# Sheet1.net
KiCad netlist of a schematic drawn in Altium Designer
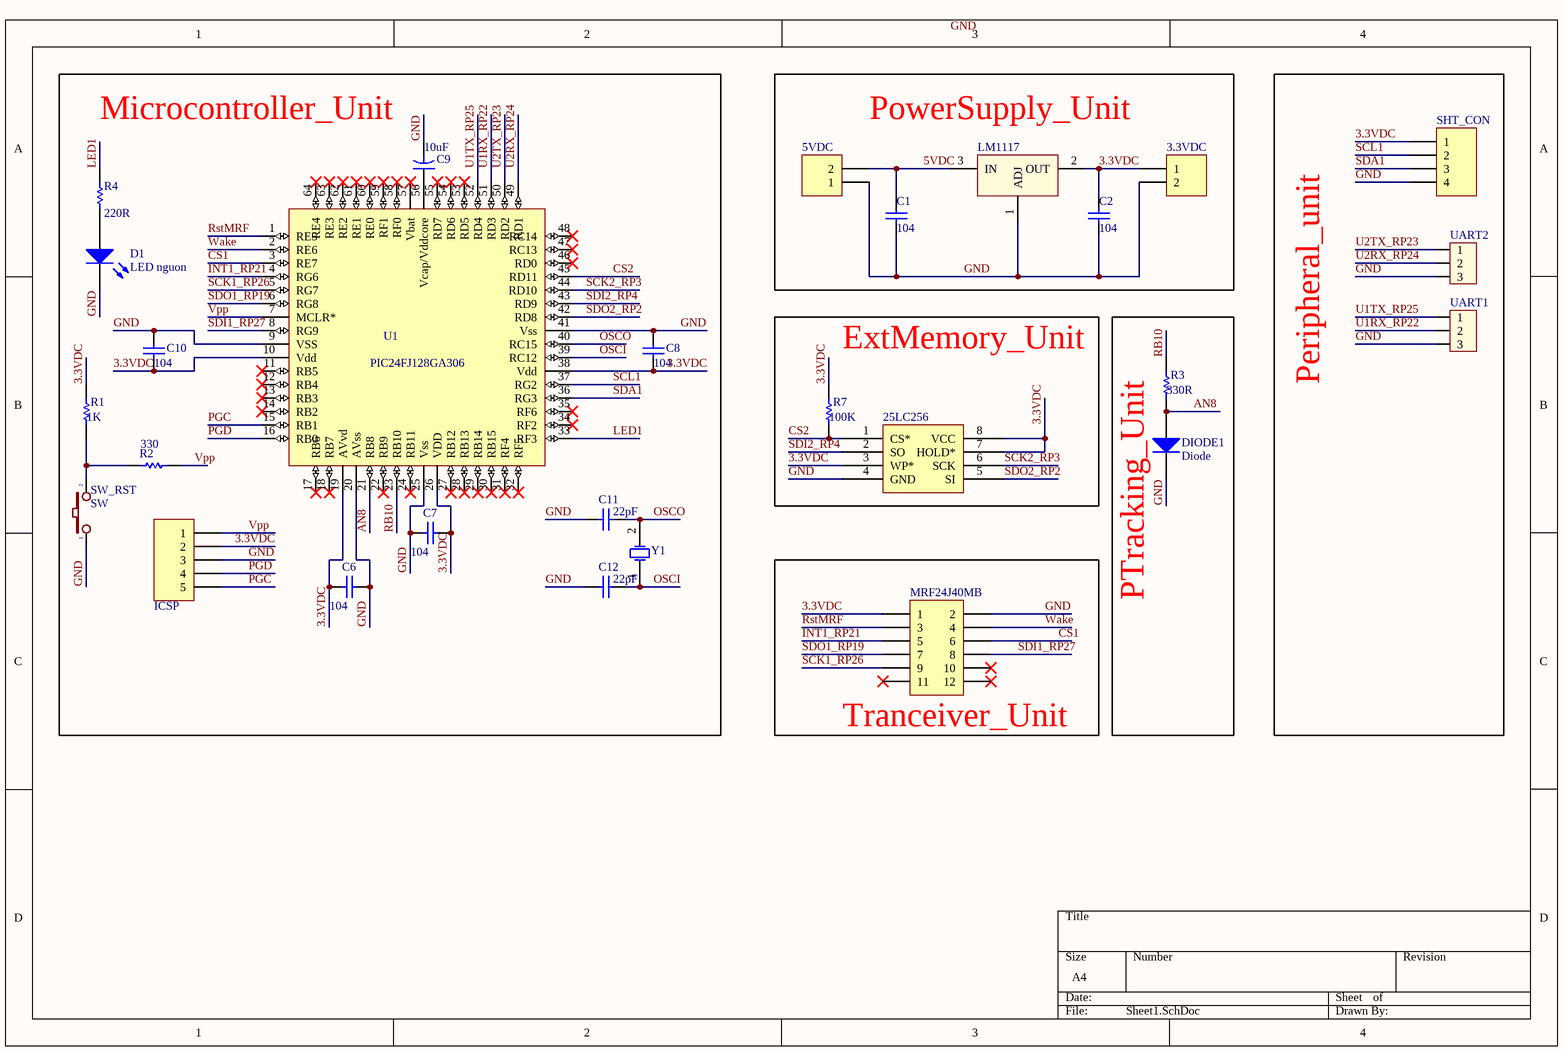
[diagram p0: Sheet1.SchDoc]

(export (version "E")
  (design (tool "Eeschema 10.0.6"))
  (components
    (comp (ref "3.3VDC")
      (value "Header 2")
      (footprint "HDR1X2")
      (description "Header, 2-Pin")
      (fields (field (name "PUBLISHER") "Altium Limited"))
      (libsource (lib "") (part "Header 2_1"))
    )
    (comp (ref "5VDC")
      (value "Header 2")
      (footprint "HDR1X2")
      (description "Header, 2-Pin")
      (fields (field (name "PUBLISHER") "Altium Limited"))
      (libsource (lib "Miscellaneous Connectors") (part "Header 2"))
    )
    (comp (ref "25LC256") (value "25LC256") (footprint "DIP-8") (libsource (lib "25LC256") (part "25LC256")))
    (comp (ref "C1")
      (value "104")
      (footprint "C0805")
      (description "Capacitor")
      (fields (field (name "Comment") "Cap") (field (name "PUBLISHER") "Altium Limited"))
      (libsource (lib "Miscellaneous Devices") (part "Cap"))
    )
    (comp (ref "C2")
      (value "104")
      (footprint "C0805")
      (description "Capacitor")
      (fields (field (name "Comment") "Cap") (field (name "PUBLISHER") "Altium Limited"))
      (libsource (lib "Miscellaneous Devices") (part "Cap"))
    )
    (comp (ref "C6")
      (value "104")
      (footprint "C0805")
      (description "Capacitor")
      (fields (field (name "Comment") "Cap") (field (name "PUBLISHER") "Altium Limited"))
      (libsource (lib "Miscellaneous Devices") (part "Cap"))
    )
    (comp (ref "C7")
      (value "104")
      (footprint "C0805")
      (description "Capacitor")
      (fields (field (name "Comment") "Cap") (field (name "PUBLISHER") "Altium Limited"))
      (libsource (lib "Miscellaneous Devices") (part "Cap"))
    )
    (comp (ref "C8")
      (value "104")
      (footprint "C0805")
      (description "Capacitor")
      (fields (field (name "Comment") "Cap") (field (name "PUBLISHER") "Altium Limited"))
      (libsource (lib "Miscellaneous Devices") (part "Cap"))
    )
    (comp (ref "C9")
      (value "10uF")
      (footprint "CAP P 6.3x5.4")
      (description "Capacitor")
      (fields (field (name "Comment") "Cap2") (field (name "PUBLISHER") "Altium Limited"))
      (libsource (lib "Miscellaneous Devices") (part "Cap2"))
    )
    (comp (ref "C10")
      (value "104")
      (footprint "C0805")
      (description "Capacitor")
      (fields (field (name "Comment") "Cap") (field (name "PUBLISHER") "Altium Limited"))
      (libsource (lib "Miscellaneous Devices") (part "Cap"))
    )
    (comp (ref "C11")
      (value "22pF")
      (footprint "C0805")
      (description "Capacitor")
      (fields (field (name "Comment") "Cap") (field (name "PUBLISHER") "Altium Limited"))
      (libsource (lib "Miscellaneous Devices") (part "Cap"))
    )
    (comp (ref "C12")
      (value "22pF")
      (footprint "C0805")
      (description "Capacitor")
      (fields (field (name "Comment") "Cap") (field (name "PUBLISHER") "Altium Limited"))
      (libsource (lib "Miscellaneous Devices") (part "Cap"))
    )
    (comp (ref "D1")
      (value "LED nguon")
      (footprint "LED3mm")
      (description "Typical INFRARED GaAs LED")
      (fields (field (name "PUBLISHER") "Altium Limited"))
      (libsource (lib "Miscellaneous Devices") (part "LED0"))
    )
    (comp (ref "DIODE1")
      (value "Diode")
      (footprint "DZ0.5A")
      (description "Default Diode")
      (fields (field (name "PUBLISHER") "Altium Limited"))
      (libsource (lib "Miscellaneous Devices") (part "Diode"))
    )
    (comp (ref "ICSP")
      (value "ICSP")
      (footprint "CON5")
      (description "Header, 5-Pin")
      (fields (field (name "PUBLISHER") "Altium Limited"))
      (libsource (lib "Miscellaneous Connectors") (part "Header 5"))
    )
    (comp (ref "LM1117")
      (value "LM317")
      (footprint "SOT223-4N")
      (description "Adj Voltage +1.2 -> +37V")
      (libsource (lib "syhaunguyen") (part "LM317"))
    )
    (comp (ref "MRF24J40MB")
      (value "Header 6X2")
      (footprint "MRF24J40MB_board_mini")
      (description "Header, 6-Pin, Dual row")
      (fields (field (name "PUBLISHER") "Altium Limited"))
      (libsource (lib "Miscellaneous Connectors") (part "Header 6X2"))
    )
    (comp (ref "R1")
      (value "1K")
      (footprint "C0805")
      (description "Resistor")
      (fields (field (name "Comment") "Res1") (field (name "PUBLISHER") "Altium Limited"))
      (libsource (lib "Miscellaneous Devices") (part "Res1"))
    )
    (comp (ref "R2")
      (value "330")
      (footprint "C0805")
      (description "Resistor")
      (fields (field (name "Comment") "res") (field (name "PUBLISHER") "Altium Limited"))
      (libsource (lib "Miscellaneous Devices") (part "Res1"))
    )
    (comp (ref "R3")
      (value "330R")
      (footprint "C0805")
      (description "Resistor")
      (fields (field (name "Comment") "Res1") (field (name "PUBLISHER") "Altium Limited"))
      (libsource (lib "Miscellaneous Devices") (part "Res1"))
    )
    (comp (ref "R4")
      (value "220R")
      (footprint "C0805")
      (description "Resistor")
      (fields (field (name "Comment") "Res1") (field (name "PUBLISHER") "Altium Limited"))
      (libsource (lib "Miscellaneous Devices") (part "Res1"))
    )
    (comp (ref "R7")
      (value "100K")
      (footprint "C0805")
      (description "Semiconductor Resistor")
      (fields (field (name "Comment") "Res Semi") (field (name "PUBLISHER") "Altium Limited"))
      (libsource (lib "Miscellaneous Devices") (part "Res Semi"))
    )
    (comp (ref "SHT_CON")
      (value "SHT10 conector")
      (footprint "CON4")
      (description "Header, 4-Pin")
      (fields (field (name "PUBLISHER") "Altium Limited"))
      (libsource (lib "Miscellaneous Connectors") (part "Header 4"))
    )
    (comp (ref "SW_RST")
      (value "SW")
      (footprint "SW2")
      (description "Switch button 2 pin")
      (libsource (lib "syhaunguyen") (part "SW2"))
    )
    (comp (ref "U1")
      (value "PIC24FJ128GA306")
      (footprint "TQFP-PT64_N")
      (libsource (lib "Mylibbrary") (part "PIC24FJ128GA306"))
    )
    (comp (ref "UART1")
      (value "UART1")
      (footprint "CON3")
      (description "Connector 3")
      (libsource (lib "syhaunguyen") (part "Con3"))
    )
    (comp (ref "UART2")
      (value "UART2")
      (footprint "CON3")
      (description "Connector 3")
      (libsource (lib "syhaunguyen") (part "Con3"))
    )
    (comp (ref "Y1")
      (value "XTAL")
      (footprint "XT2")
      (description "Crystal Oscillator")
      (fields (field (name "PUBLISHER") "Altium Limited"))
      (libsource (lib "Miscellaneous Devices") (part "XTAL"))
    )
  )
  (nets
    (net (code "1") (name "/3.3VDC") (class "Default")
      (node (ref "25LC256") (pin "3") (pinfunction "WP*_3") (pintype "passive"))
      (node (ref "25LC256") (pin "7") (pinfunction "HOLD*_7") (pintype "passive"))
      (node (ref "25LC256") (pin "8") (pinfunction "VCC_8") (pintype "power_in"))
      (node (ref "3.3VDC") (pin "1") (pinfunction "1_1") (pintype "passive"))
      (node (ref "C10") (pin "1") (pinfunction "1_1") (pintype "passive"))
      (node (ref "C2") (pin "2") (pinfunction "2_2") (pintype "passive"))
      (node (ref "C6") (pin "1") (pinfunction "1_1") (pintype "passive"))
      (node (ref "C7") (pin "2") (pinfunction "2_2") (pintype "passive"))
      (node (ref "C8") (pin "1") (pinfunction "1_1") (pintype "passive"))
      (node (ref "ICSP") (pin "2") (pinfunction "2_2") (pintype "passive"))
      (node (ref "LM1117") (pin "2") (pinfunction "OUT_2") (pintype "passive"))
      (node (ref "MRF24J40MB") (pin "1") (pinfunction "1_1") (pintype "passive"))
      (node (ref "R1") (pin "2") (pinfunction "2_2") (pintype "passive"))
      (node (ref "R7") (pin "2") (pinfunction "2_2") (pintype "passive"))
      (node (ref "SHT_CON") (pin "1") (pinfunction "1_1") (pintype "passive"))
      (node (ref "U1") (pin "10") (pinfunction "Vdd_10") (pintype "passive"))
      (node (ref "U1") (pin "19") (pinfunction "AVvd_19") (pintype "power_in"))
      (node (ref "U1") (pin "26") (pinfunction "VDD_26") (pintype "power_in"))
      (node (ref "U1") (pin "38") (pinfunction "Vdd_38") (pintype "power_in"))
    )
    (net (code "2") (name "/5VDC") (class "Default")
      (node (ref "5VDC") (pin "2") (pinfunction "2_2") (pintype "passive"))
      (node (ref "C1") (pin "2") (pinfunction "2_2") (pintype "passive"))
      (node (ref "LM1117") (pin "3") (pinfunction "IN_3") (pintype "passive"))
    )
    (net (code "3") (name "/AN8") (class "Default")
      (node (ref "DIODE1") (pin "1") (pinfunction "A_1") (pintype "passive"))
      (node (ref "R3") (pin "1") (pinfunction "1_1") (pintype "passive"))
      (node (ref "U1") (pin "21") (pinfunction "RB8_21") (pintype "bidirectional"))
    )
    (net (code "4") (name "/CS1") (class "Default")
      (node (ref "MRF24J40MB") (pin "6") (pinfunction "6_6") (pintype "passive"))
      (node (ref "U1") (pin "3") (pinfunction "RE7_3") (pintype "bidirectional"))
    )
    (net (code "5") (name "/CS2") (class "Default")
      (node (ref "25LC256") (pin "1") (pinfunction "CS*_1") (pintype "passive"))
      (node (ref "R7") (pin "1") (pinfunction "1_1") (pintype "passive"))
      (node (ref "U1") (pin "45") (pinfunction "RD11_45") (pintype "bidirectional"))
    )
    (net (code "6") (name "/GND") (class "Default")
      (node (ref "25LC256") (pin "4") (pinfunction "GND_4") (pintype "power_in"))
      (node (ref "3.3VDC") (pin "2") (pinfunction "2_2") (pintype "passive"))
      (node (ref "5VDC") (pin "1") (pinfunction "1_1") (pintype "passive"))
      (node (ref "C1") (pin "1") (pinfunction "1_1") (pintype "passive"))
      (node (ref "C10") (pin "2") (pinfunction "2_2") (pintype "passive"))
      (node (ref "C11") (pin "1") (pinfunction "1_1") (pintype "passive"))
      (node (ref "C12") (pin "1") (pinfunction "1_1") (pintype "passive"))
      (node (ref "C2") (pin "1") (pinfunction "1_1") (pintype "passive"))
      (node (ref "C6") (pin "2") (pinfunction "2_2") (pintype "passive"))
      (node (ref "C7") (pin "1") (pinfunction "1_1") (pintype "passive"))
      (node (ref "C8") (pin "2") (pinfunction "2_2") (pintype "passive"))
      (node (ref "C9") (pin "2") (pinfunction "2_2") (pintype "passive"))
      (node (ref "D1") (pin "2") (pinfunction "K_2") (pintype "passive"))
      (node (ref "DIODE1") (pin "2") (pinfunction "K_2") (pintype "passive"))
      (node (ref "ICSP") (pin "3") (pinfunction "3_3") (pintype "passive"))
      (node (ref "LM1117") (pin "1") (pinfunction "ADJ_1") (pintype "passive"))
      (node (ref "MRF24J40MB") (pin "2") (pinfunction "2_2") (pintype "passive"))
      (node (ref "SHT_CON") (pin "4") (pinfunction "4_4") (pintype "passive"))
      (node (ref "SW_RST") (pin "1") (pinfunction "1_1") (pintype "passive"))
      (node (ref "U1") (pin "20") (pinfunction "AVss_20") (pintype "power_in"))
      (node (ref "U1") (pin "25") (pinfunction "Vss_25") (pintype "power_in"))
      (node (ref "U1") (pin "41") (pinfunction "Vss_41") (pintype "power_in"))
      (node (ref "U1") (pin "9") (pinfunction "VSS_9") (pintype "power_in"))
      (node (ref "UART1") (pin "3") (pinfunction "3_3") (pintype "passive"))
      (node (ref "UART2") (pin "3") (pinfunction "3_3") (pintype "passive"))
    )
    (net (code "7") (name "/INT1_RP21") (class "Default")
      (node (ref "MRF24J40MB") (pin "5") (pinfunction "5_5") (pintype "passive"))
      (node (ref "U1") (pin "4") (pinfunction "RG6_4") (pintype "bidirectional"))
    )
    (net (code "8") (name "/LED1") (class "Default")
      (node (ref "R4") (pin "2") (pinfunction "2_2") (pintype "passive"))
      (node (ref "U1") (pin "33") (pinfunction "RF3_33") (pintype "bidirectional"))
    )
    (net (code "9") (name "/OSCI") (class "Default")
      (node (ref "C12") (pin "2") (pinfunction "2_2") (pintype "passive"))
      (node (ref "U1") (pin "39") (pinfunction "RC12_39") (pintype "bidirectional"))
      (node (ref "Y1") (pin "1") (pinfunction "OSC1_1") (pintype "passive"))
    )
    (net (code "10") (name "/OSCO") (class "Default")
      (node (ref "C11") (pin "2") (pinfunction "2_2") (pintype "passive"))
      (node (ref "U1") (pin "40") (pinfunction "RC15_40") (pintype "bidirectional"))
      (node (ref "Y1") (pin "2") (pinfunction "OSC2_2") (pintype "passive"))
    )
    (net (code "11") (name "/PGC") (class "Default")
      (node (ref "ICSP") (pin "5") (pinfunction "5_5") (pintype "passive"))
      (node (ref "U1") (pin "15") (pinfunction "RB1_15") (pintype "bidirectional"))
    )
    (net (code "12") (name "/PGD") (class "Default")
      (node (ref "ICSP") (pin "4") (pinfunction "4_4") (pintype "passive"))
      (node (ref "U1") (pin "16") (pinfunction "RB0_16") (pintype "bidirectional"))
    )
    (net (code "13") (name "/RB10") (class "Default")
      (node (ref "R3") (pin "2") (pinfunction "2_2") (pintype "passive"))
      (node (ref "U1") (pin "23") (pinfunction "RB10_23") (pintype "bidirectional"))
    )
    (net (code "14") (name "/RstMRF") (class "Default")
      (node (ref "MRF24J40MB") (pin "3") (pinfunction "3_3") (pintype "passive"))
      (node (ref "U1") (pin "1") (pinfunction "RE5_1") (pintype "bidirectional"))
    )
    (net (code "15") (name "/SCK1_RP26") (class "Default")
      (node (ref "MRF24J40MB") (pin "9") (pinfunction "9_9") (pintype "passive"))
      (node (ref "U1") (pin "5") (pinfunction "RG7_5") (pintype "bidirectional"))
    )
    (net (code "16") (name "/SCK2_RP3") (class "Default")
      (node (ref "25LC256") (pin "6") (pinfunction "SCK_6") (pintype "passive"))
      (node (ref "U1") (pin "44") (pinfunction "RD10_44") (pintype "bidirectional"))
    )
    (net (code "17") (name "/SCL1") (class "Default")
      (node (ref "SHT_CON") (pin "2") (pinfunction "2_2") (pintype "passive"))
      (node (ref "U1") (pin "37") (pinfunction "RG2_37") (pintype "bidirectional"))
    )
    (net (code "18") (name "/SDA1") (class "Default")
      (node (ref "SHT_CON") (pin "3") (pinfunction "3_3") (pintype "passive"))
      (node (ref "U1") (pin "36") (pinfunction "RG3_36") (pintype "bidirectional"))
    )
    (net (code "19") (name "/SDI1_RP27") (class "Default")
      (node (ref "MRF24J40MB") (pin "8") (pinfunction "8_8") (pintype "passive"))
      (node (ref "U1") (pin "8") (pinfunction "RG9_8") (pintype "bidirectional"))
    )
    (net (code "20") (name "/SDI2_RP4") (class "Default")
      (node (ref "25LC256") (pin "2") (pinfunction "SO_2") (pintype "passive"))
      (node (ref "U1") (pin "43") (pinfunction "RD9_43") (pintype "bidirectional"))
    )
    (net (code "21") (name "/SDO1_RP19") (class "Default")
      (node (ref "MRF24J40MB") (pin "7") (pinfunction "7_7") (pintype "passive"))
      (node (ref "U1") (pin "6") (pinfunction "RG8_6") (pintype "bidirectional"))
    )
    (net (code "22") (name "/SDO2_RP2") (class "Default")
      (node (ref "25LC256") (pin "5") (pinfunction "SI_5") (pintype "passive"))
      (node (ref "U1") (pin "42") (pinfunction "RD8_42") (pintype "bidirectional"))
    )
    (net (code "23") (name "/U1RX_RP22") (class "Default")
      (node (ref "U1") (pin "51") (pinfunction "RD3_51") (pintype "bidirectional"))
      (node (ref "UART1") (pin "2") (pinfunction "2_2") (pintype "passive"))
    )
    (net (code "24") (name "/U1TX_RP25") (class "Default")
      (node (ref "U1") (pin "52") (pinfunction "RD4_52") (pintype "bidirectional"))
      (node (ref "UART1") (pin "1") (pinfunction "1_1") (pintype "passive"))
    )
    (net (code "25") (name "/U2RX_RP24") (class "Default")
      (node (ref "U1") (pin "49") (pinfunction "RD1_49") (pintype "bidirectional"))
      (node (ref "UART2") (pin "2") (pinfunction "2_2") (pintype "passive"))
    )
    (net (code "26") (name "/U2TX_RP23") (class "Default")
      (node (ref "U1") (pin "50") (pinfunction "RD2_50") (pintype "bidirectional"))
      (node (ref "UART2") (pin "1") (pinfunction "1_1") (pintype "passive"))
    )
    (net (code "27") (name "/Vpp") (class "Default")
      (node (ref "ICSP") (pin "1") (pinfunction "1_1") (pintype "passive"))
      (node (ref "R2") (pin "2") (pinfunction "2_2") (pintype "passive"))
      (node (ref "U1") (pin "7") (pinfunction "MCLR*_7") (pintype "passive"))
    )
    (net (code "28") (name "/Wake") (class "Default")
      (node (ref "MRF24J40MB") (pin "4") (pinfunction "4_4") (pintype "passive"))
      (node (ref "U1") (pin "2") (pinfunction "RE6_2") (pintype "bidirectional"))
    )
    (net (code "29") (name "Net-(D1-A)") (class "Default")
      (node (ref "D1") (pin "1") (pinfunction "A_1") (pintype "passive"))
      (node (ref "R4") (pin "1") (pinfunction "1_1") (pintype "passive"))
    )
    (net (code "30") (name "Net-(R1-Pad1)") (class "Default")
      (node (ref "R1") (pin "1") (pinfunction "1_1") (pintype "passive"))
      (node (ref "R2") (pin "1") (pinfunction "1_1") (pintype "passive"))
      (node (ref "SW_RST") (pin "2") (pinfunction "2_2") (pintype "passive"))
    )
    (net (code "31") (name "Net-(U1-Vcap{slash}Vddcore)") (class "Default")
      (node (ref "C9") (pin "1") (pinfunction "1_1") (pintype "passive"))
      (node (ref "U1") (pin "56") (pinfunction "Vcap/Vddcore_56") (pintype "power_in"))
    )
    (net (code "32") (name "unconnected-(MRF24J40MB-Pad10)") (class "Default")
      (node (ref "MRF24J40MB") (pin "10") (pinfunction "10_10") (pintype "passive+no_connect"))
    )
    (net (code "33") (name "unconnected-(MRF24J40MB-Pad11)") (class "Default")
      (node (ref "MRF24J40MB") (pin "11") (pinfunction "11_11") (pintype "passive+no_connect"))
    )
    (net (code "34") (name "unconnected-(MRF24J40MB-Pad12)") (class "Default")
      (node (ref "MRF24J40MB") (pin "12") (pinfunction "12_12") (pintype "passive+no_connect"))
    )
    (net (code "35") (name "unconnected-(U1-RB2-Pad14)") (class "Default")
      (node (ref "U1") (pin "14") (pinfunction "RB2_14") (pintype "bidirectional+no_connect"))
    )
    (net (code "36") (name "unconnected-(U1-RB3-Pad13)") (class "Default")
      (node (ref "U1") (pin "13") (pinfunction "RB3_13") (pintype "bidirectional+no_connect"))
    )
    (net (code "37") (name "unconnected-(U1-RB4-Pad12)") (class "Default")
      (node (ref "U1") (pin "12") (pinfunction "RB4_12") (pintype "bidirectional+no_connect"))
    )
    (net (code "38") (name "unconnected-(U1-RB5-Pad11)") (class "Default")
      (node (ref "U1") (pin "11") (pinfunction "RB5_11") (pintype "bidirectional+no_connect"))
    )
    (net (code "39") (name "unconnected-(U1-RB6-Pad17)") (class "Default")
      (node (ref "U1") (pin "17") (pinfunction "RB6_17") (pintype "bidirectional+no_connect"))
    )
    (net (code "40") (name "unconnected-(U1-RB7-Pad18)") (class "Default")
      (node (ref "U1") (pin "18") (pinfunction "RB7_18") (pintype "bidirectional+no_connect"))
    )
    (net (code "41") (name "unconnected-(U1-RB9-Pad22)") (class "Default")
      (node (ref "U1") (pin "22") (pinfunction "RB9_22") (pintype "bidirectional+no_connect"))
    )
    (net (code "42") (name "unconnected-(U1-RB11-Pad24)") (class "Default")
      (node (ref "U1") (pin "24") (pinfunction "RB11_24") (pintype "bidirectional+no_connect"))
    )
    (net (code "43") (name "unconnected-(U1-RB12-Pad27)") (class "Default")
      (node (ref "U1") (pin "27") (pinfunction "RB12_27") (pintype "bidirectional+no_connect"))
    )
    (net (code "44") (name "unconnected-(U1-RB13-Pad28)") (class "Default")
      (node (ref "U1") (pin "28") (pinfunction "RB13_28") (pintype "bidirectional+no_connect"))
    )
    (net (code "45") (name "unconnected-(U1-RB14-Pad29)") (class "Default")
      (node (ref "U1") (pin "29") (pinfunction "RB14_29") (pintype "bidirectional+no_connect"))
    )
    (net (code "46") (name "unconnected-(U1-RB15-Pad30)") (class "Default")
      (node (ref "U1") (pin "30") (pinfunction "RB15_30") (pintype "bidirectional+no_connect"))
    )
    (net (code "47") (name "unconnected-(U1-RC13-Pad47)") (class "Default")
      (node (ref "U1") (pin "47") (pinfunction "RC13_47") (pintype "bidirectional+no_connect"))
    )
    (net (code "48") (name "unconnected-(U1-RC14-Pad48)") (class "Default")
      (node (ref "U1") (pin "48") (pinfunction "RC14_48") (pintype "bidirectional+no_connect"))
    )
    (net (code "49") (name "unconnected-(U1-RD0-Pad46)") (class "Default")
      (node (ref "U1") (pin "46") (pinfunction "RD0_46") (pintype "bidirectional+no_connect"))
    )
    (net (code "50") (name "unconnected-(U1-RD5-Pad53)") (class "Default")
      (node (ref "U1") (pin "53") (pinfunction "RD5_53") (pintype "bidirectional+no_connect"))
    )
    (net (code "51") (name "unconnected-(U1-RD6-Pad54)") (class "Default")
      (node (ref "U1") (pin "54") (pinfunction "RD6_54") (pintype "bidirectional+no_connect"))
    )
    (net (code "52") (name "unconnected-(U1-RD7-Pad55)") (class "Default")
      (node (ref "U1") (pin "55") (pinfunction "RD7_55") (pintype "bidirectional+no_connect"))
    )
    (net (code "53") (name "unconnected-(U1-RE0-Pad60)") (class "Default")
      (node (ref "U1") (pin "60") (pinfunction "RE0_60") (pintype "bidirectional+no_connect"))
    )
    (net (code "54") (name "unconnected-(U1-RE1-Pad61)") (class "Default")
      (node (ref "U1") (pin "61") (pinfunction "RE1_61") (pintype "bidirectional+no_connect"))
    )
    (net (code "55") (name "unconnected-(U1-RE2-Pad62)") (class "Default")
      (node (ref "U1") (pin "62") (pinfunction "RE2_62") (pintype "bidirectional+no_connect"))
    )
    (net (code "56") (name "unconnected-(U1-RE3-Pad63)") (class "Default")
      (node (ref "U1") (pin "63") (pinfunction "RE3_63") (pintype "bidirectional+no_connect"))
    )
    (net (code "57") (name "unconnected-(U1-RE4-Pad64)") (class "Default")
      (node (ref "U1") (pin "64") (pinfunction "RE4_64") (pintype "bidirectional+no_connect"))
    )
    (net (code "58") (name "unconnected-(U1-RF0-Pad58)") (class "Default")
      (node (ref "U1") (pin "58") (pinfunction "RF0_58") (pintype "bidirectional+no_connect"))
    )
    (net (code "59") (name "unconnected-(U1-RF1-Pad59)") (class "Default")
      (node (ref "U1") (pin "59") (pinfunction "RF1_59") (pintype "bidirectional+no_connect"))
    )
    (net (code "60") (name "unconnected-(U1-RF2-Pad34)") (class "Default")
      (node (ref "U1") (pin "34") (pinfunction "RF2_34") (pintype "bidirectional+no_connect"))
    )
    (net (code "61") (name "unconnected-(U1-RF4-Pad31)") (class "Default")
      (node (ref "U1") (pin "31") (pinfunction "RF4_31") (pintype "bidirectional+no_connect"))
    )
    (net (code "62") (name "unconnected-(U1-RF5-Pad32)") (class "Default")
      (node (ref "U1") (pin "32") (pinfunction "RF5_32") (pintype "bidirectional+no_connect"))
    )
    (net (code "63") (name "unconnected-(U1-RF6-Pad35)") (class "Default")
      (node (ref "U1") (pin "35") (pinfunction "RF6_35") (pintype "bidirectional+no_connect"))
    )
    (net (code "64") (name "unconnected-(U1-Vbat-Pad57)") (class "Default")
      (node (ref "U1") (pin "57") (pinfunction "Vbat_57") (pintype "power_in+no_connect"))
    )
  )
)
